# PWR.net
KiCad netlist of a schematic drawn in Altium Designer
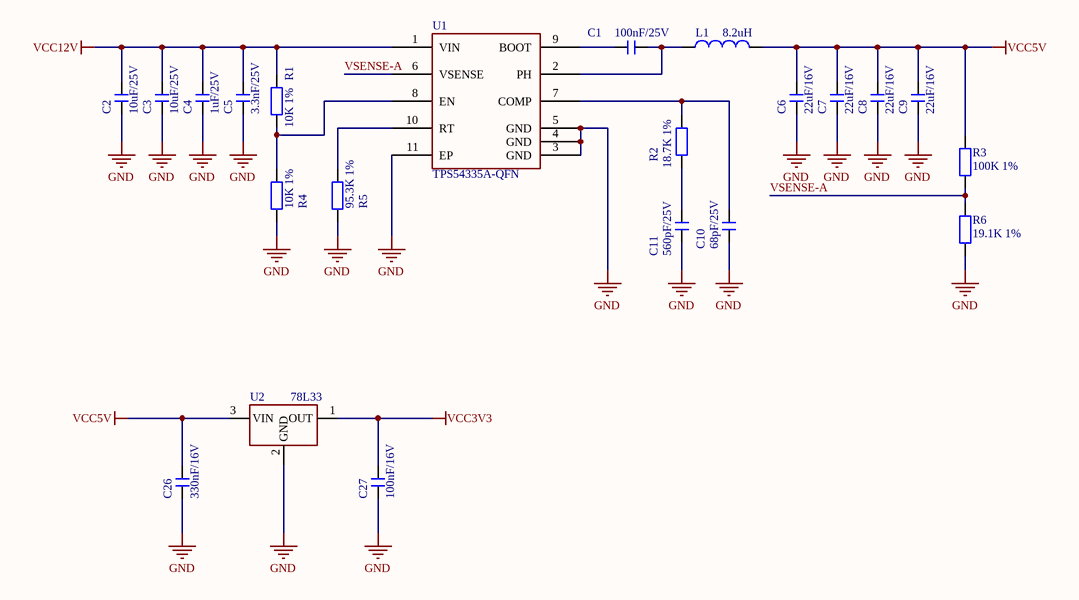
[diagram p0: PWR.SchDoc]

(export (version "E")
  (design (tool "Eeschema 10.0.6"))
  (components
    (comp (ref "C1")
      (value "100nF/25V")
      (footprint "C0603_L")
      (description "无极性贴片电容")
      (fields (field (name "版权归属") "源创客"))
      (libsource (lib "Capacitor") (part "C"))
    )
    (comp (ref "C2")
      (value "10uF/25V")
      (footprint "C0603_L")
      (description "无极性贴片电容")
      (fields (field (name "版权归属") "源创客"))
      (libsource (lib "Capacitor") (part "C"))
    )
    (comp (ref "C3")
      (value "10uF/25V")
      (footprint "C0603_L")
      (description "无极性贴片电容")
      (fields (field (name "版权归属") "源创客"))
      (libsource (lib "Capacitor") (part "C"))
    )
    (comp (ref "C4")
      (value "1uF/25V")
      (footprint "C0603_L")
      (description "无极性贴片电容")
      (fields (field (name "版权归属") "源创客"))
      (libsource (lib "Capacitor") (part "C"))
    )
    (comp (ref "C5")
      (value "3.3nF/25V")
      (footprint "C0603_L")
      (description "无极性贴片电容")
      (fields (field (name "版权归属") "源创客"))
      (libsource (lib "Capacitor") (part "C"))
    )
    (comp (ref "C6")
      (value "22uF/16V")
      (footprint "C0603_L")
      (description "无极性贴片电容")
      (fields (field (name "版权归属") "源创客"))
      (libsource (lib "Capacitor") (part "C"))
    )
    (comp (ref "C7")
      (value "22uF/16V")
      (footprint "C0603_L")
      (description "无极性贴片电容")
      (fields (field (name "版权归属") "源创客"))
      (libsource (lib "Capacitor") (part "C"))
    )
    (comp (ref "C8")
      (value "22uF/16V")
      (footprint "C0603_L")
      (description "无极性贴片电容")
      (fields (field (name "版权归属") "源创客"))
      (libsource (lib "Capacitor") (part "C"))
    )
    (comp (ref "C9")
      (value "22uF/16V")
      (footprint "C0603_L")
      (description "无极性贴片电容")
      (fields (field (name "版权归属") "源创客"))
      (libsource (lib "Capacitor") (part "C"))
    )
    (comp (ref "C10")
      (value "68pF/25V")
      (footprint "C0603_L")
      (description "无极性贴片电容")
      (fields (field (name "版权归属") "源创客"))
      (libsource (lib "Capacitor") (part "C"))
    )
    (comp (ref "C11")
      (value "560pF/25V")
      (footprint "C0603_L")
      (description "无极性贴片电容")
      (fields (field (name "版权归属") "源创客"))
      (libsource (lib "Capacitor") (part "C"))
    )
    (comp (ref "C26")
      (value "330nF/16V")
      (footprint "C0603_L")
      (description "无极性贴片电容")
      (fields (field (name "版权归属") "源创客"))
      (libsource (lib "Capacitor") (part "C"))
    )
    (comp (ref "C27")
      (value "100nF/16V")
      (footprint "C0603_L")
      (description "无极性贴片电容")
      (fields (field (name "版权归属") "源创客"))
      (libsource (lib "Capacitor") (part "C"))
    )
    (comp (ref "L1")
      (value "8.2uH")
      (footprint "NR4020")
      (description "小功率贴片电感")
      (fields (field (name "版权归属") "源创客"))
      (libsource (lib "Inductor") (part "L"))
    )
    (comp (ref "R1")
      (value "10K 1%")
      (footprint "R0603_L")
      (description "贴片电阻")
      (fields (field (name "版权归属") "源创客"))
      (libsource (lib "Resistor") (part "R"))
    )
    (comp (ref "R2")
      (value "18.7K 1%")
      (footprint "R0603_L")
      (description "贴片电阻")
      (fields (field (name "版权归属") "源创客"))
      (libsource (lib "Resistor") (part "R"))
    )
    (comp (ref "R3")
      (value "100K 1%")
      (footprint "R0603_L")
      (description "贴片电阻")
      (fields (field (name "版权归属") "源创客"))
      (libsource (lib "Resistor") (part "R"))
    )
    (comp (ref "R4")
      (value "10K 1%")
      (footprint "R0603_L")
      (description "贴片电阻")
      (fields (field (name "版权归属") "源创客"))
      (libsource (lib "Resistor") (part "R"))
    )
    (comp (ref "R5")
      (value "95.3K 1%")
      (footprint "R0603_L")
      (description "贴片电阻")
      (fields (field (name "版权归属") "源创客"))
      (libsource (lib "Resistor") (part "R"))
    )
    (comp (ref "R6")
      (value "19.1K 1%")
      (footprint "R0603_L")
      (description "贴片电阻")
      (fields (field (name "版权归属") "源创客"))
      (libsource (lib "Resistor") (part "R"))
    )
    (comp (ref "U1")
      (value "TPS54335A-QFN")
      (footprint "VSON-10_L3.0-W3.0-P0.50-TL-EP")
      (description "BUCK")
      (libsource (lib "DCDC Convert") (part "TPS54335A-QFN"))
    )
    (comp (ref "U2") (value "78L33") (footprint "SOT89_L") (libsource (lib "LDO") (part "78L33")))
  )
  (nets
    (net (code "1") (name "/VSENSE-A") (class "Default")
      (node (ref "R3") (pin "2") (pinfunction "2_2") (pintype "passive"))
      (node (ref "R6") (pin "1") (pinfunction "1_1") (pintype "passive"))
      (node (ref "U1") (pin "6") (pinfunction "VSENSE_6") (pintype "passive"))
    )
    (net (code "2") (name "GND") (class "Default")
      (node (ref "C10") (pin "1") (pinfunction "1_1") (pintype "passive"))
      (node (ref "C11") (pin "1") (pinfunction "1_1") (pintype "passive"))
      (node (ref "C2") (pin "1") (pinfunction "1_1") (pintype "passive"))
      (node (ref "C26") (pin "1") (pinfunction "1_1") (pintype "passive"))
      (node (ref "C27") (pin "1") (pinfunction "1_1") (pintype "passive"))
      (node (ref "C3") (pin "1") (pinfunction "1_1") (pintype "passive"))
      (node (ref "C4") (pin "1") (pinfunction "1_1") (pintype "passive"))
      (node (ref "C5") (pin "1") (pinfunction "1_1") (pintype "passive"))
      (node (ref "C6") (pin "1") (pinfunction "1_1") (pintype "passive"))
      (node (ref "C7") (pin "1") (pinfunction "1_1") (pintype "passive"))
      (node (ref "C8") (pin "1") (pinfunction "1_1") (pintype "passive"))
      (node (ref "C9") (pin "1") (pinfunction "1_1") (pintype "passive"))
      (node (ref "R4") (pin "2") (pinfunction "2_2") (pintype "passive"))
      (node (ref "R5") (pin "2") (pinfunction "2_2") (pintype "passive"))
      (node (ref "R6") (pin "2") (pinfunction "2_2") (pintype "passive"))
      (node (ref "U1") (pin "11") (pinfunction "EP_11") (pintype "passive"))
      (node (ref "U1") (pin "3") (pinfunction "GND_3") (pintype "passive"))
      (node (ref "U1") (pin "4") (pinfunction "GND_4") (pintype "passive"))
      (node (ref "U1") (pin "5") (pinfunction "GND_5") (pintype "passive"))
      (node (ref "U2") (pin "2") (pinfunction "GND_2") (pintype "passive"))
    )
    (net (code "3") (name "Net-(C11-Pad2)") (class "Default")
      (node (ref "C11") (pin "2") (pinfunction "2_2") (pintype "passive"))
      (node (ref "R2") (pin "2") (pinfunction "2_2") (pintype "passive"))
    )
    (net (code "4") (name "Net-(U1-BOOT)") (class "Default")
      (node (ref "C1") (pin "2") (pinfunction "2_2") (pintype "passive"))
      (node (ref "U1") (pin "9") (pinfunction "BOOT_9") (pintype "passive"))
    )
    (net (code "5") (name "Net-(U1-COMP)") (class "Default")
      (node (ref "C10") (pin "2") (pinfunction "2_2") (pintype "passive"))
      (node (ref "R2") (pin "1") (pinfunction "1_1") (pintype "passive"))
      (node (ref "U1") (pin "7") (pinfunction "COMP_7") (pintype "passive"))
    )
    (net (code "6") (name "Net-(U1-EN)") (class "Default")
      (node (ref "R1") (pin "2") (pinfunction "2_2") (pintype "passive"))
      (node (ref "R4") (pin "1") (pinfunction "1_1") (pintype "passive"))
      (node (ref "U1") (pin "8") (pinfunction "EN_8") (pintype "passive"))
    )
    (net (code "7") (name "Net-(U1-PH)") (class "Default")
      (node (ref "C1") (pin "1") (pinfunction "1_1") (pintype "passive"))
      (node (ref "L1") (pin "1") (pinfunction "1_1") (pintype "passive"))
      (node (ref "U1") (pin "2") (pinfunction "PH_2") (pintype "passive"))
    )
    (net (code "8") (name "Net-(U1-RT)") (class "Default")
      (node (ref "R5") (pin "1") (pinfunction "1_1") (pintype "passive"))
      (node (ref "U1") (pin "10") (pinfunction "RT_10") (pintype "passive"))
    )
    (net (code "9") (name "VCC3V3") (class "Default")
      (node (ref "C27") (pin "2") (pinfunction "2_2") (pintype "passive"))
      (node (ref "U2") (pin "1") (pinfunction "OUT_1") (pintype "passive"))
    )
    (net (code "10") (name "VCC5V") (class "Default")
      (node (ref "C26") (pin "2") (pinfunction "2_2") (pintype "passive"))
      (node (ref "C6") (pin "2") (pinfunction "2_2") (pintype "passive"))
      (node (ref "C7") (pin "2") (pinfunction "2_2") (pintype "passive"))
      (node (ref "C8") (pin "2") (pinfunction "2_2") (pintype "passive"))
      (node (ref "C9") (pin "2") (pinfunction "2_2") (pintype "passive"))
      (node (ref "L1") (pin "2") (pinfunction "2_2") (pintype "passive"))
      (node (ref "R3") (pin "1") (pinfunction "1_1") (pintype "passive"))
      (node (ref "U2") (pin "3") (pinfunction "VIN_3") (pintype "passive"))
    )
    (net (code "11") (name "VCC12V") (class "Default")
      (node (ref "C2") (pin "2") (pinfunction "2_2") (pintype "passive"))
      (node (ref "C3") (pin "2") (pinfunction "2_2") (pintype "passive"))
      (node (ref "C4") (pin "2") (pinfunction "2_2") (pintype "passive"))
      (node (ref "C5") (pin "2") (pinfunction "2_2") (pintype "passive"))
      (node (ref "R1") (pin "1") (pinfunction "1_1") (pintype "passive"))
      (node (ref "U1") (pin "1") (pinfunction "VIN_1") (pintype "passive"))
    )
  )
)
